# 4channelsRelayv2.net
KiCad netlist of a schematic drawn in EAGLE
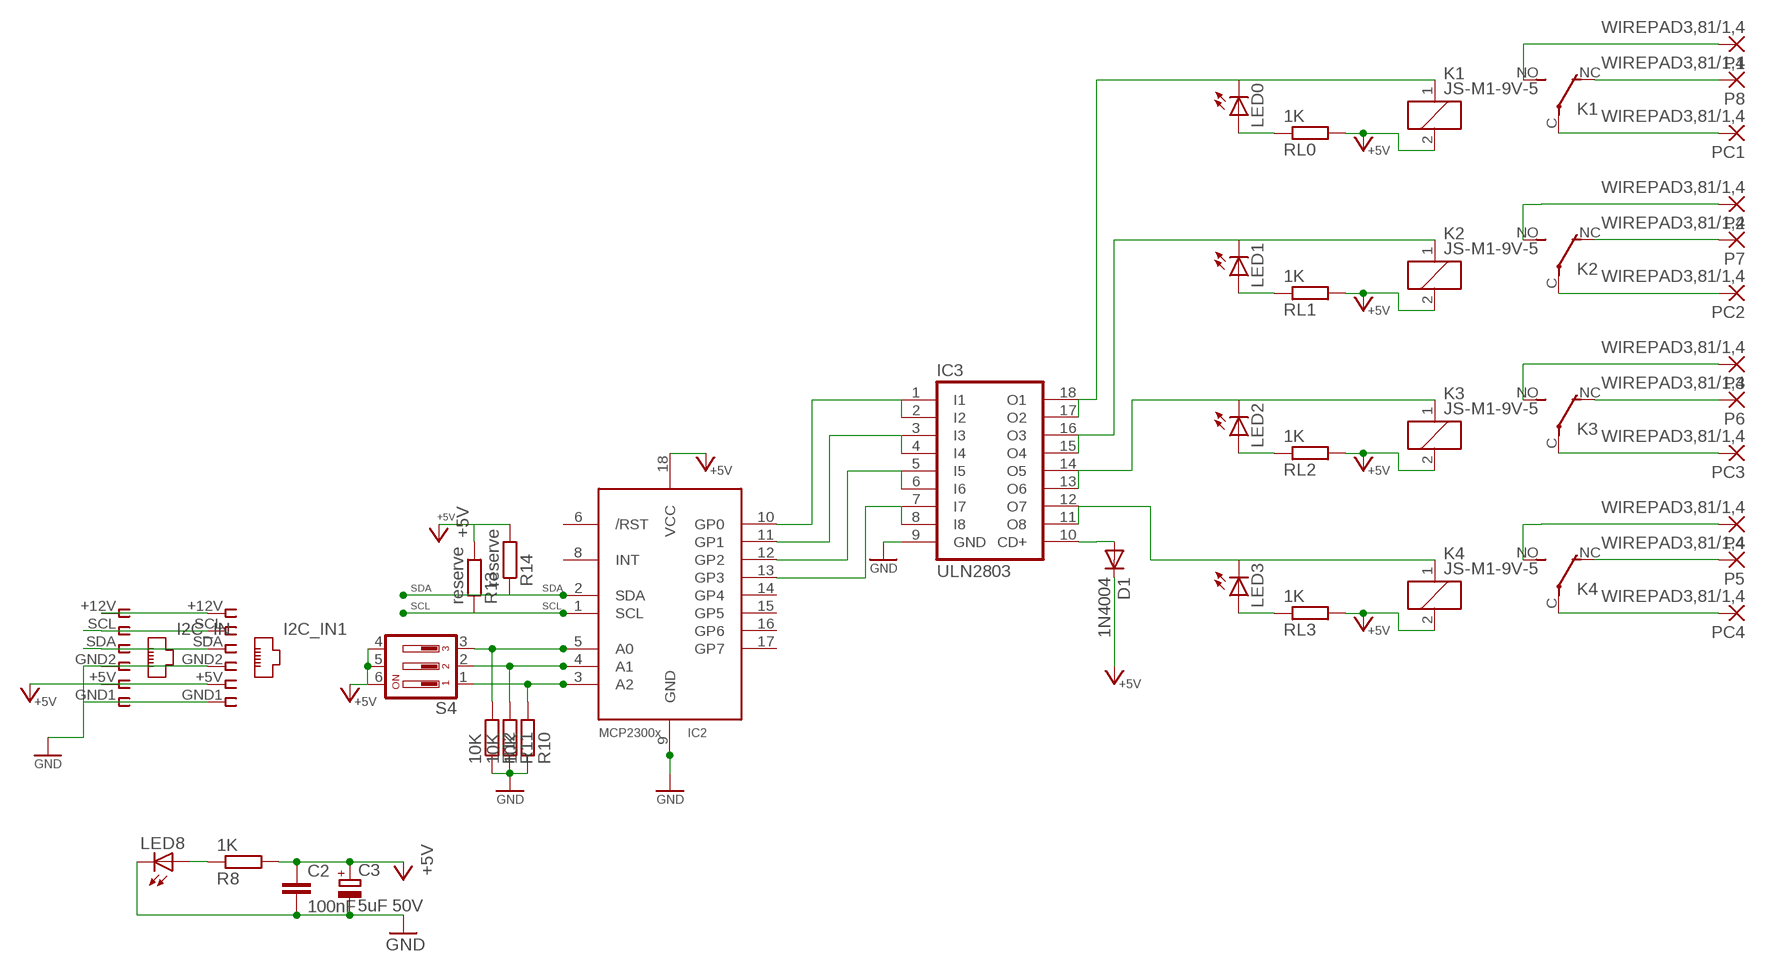
[diagram p0: schematic, sheet 1]

(export (version "E")
  (design (tool "Eeschema 10.0.6"))
  (components
    (comp (ref "C2")
      (value "100nF")
      (footprint "eagle-import:C1206")
      (libsource (lib "eagle-import") (part "C-EUC1206"))
    )
    (comp (ref "C3")
      (value "5uF 50V")
      (footprint "eagle-import:E3,5-8")
      (libsource (lib "eagle-import") (part "CPOL-EUE3.5-8"))
    )
    (comp (ref "D1")
      (value "1N4004")
      (footprint "eagle-import:DO41-10")
      (libsource (lib "eagle-import") (part "1N4004"))
    )
    (comp (ref "I2C_IN")
      (value "I2C 1")
      (footprint "eagle-import:RJ12-STRAIGHT-I2C")
      (libsource (lib "eagle-import") (part "RJ12STRAIGHT-I2C"))
    )
    (comp (ref "I2C_IN1")
      (value "I2C 2")
      (footprint "eagle-import:RJ12-STRAIGHT-I2C")
      (libsource (lib "eagle-import") (part "RJ12STRAIGHT-I2C"))
    )
    (comp (ref "IC2")
      (value "MCP2300X/P")
      (footprint "eagle-import:DIL18")
      (libsource (lib "eagle-import") (part "MCP2300X/P"))
    )
    (comp (ref "IC3")
      (value "ULN2803")
      (footprint "eagle-import:DIL18")
      (libsource (lib "eagle-import") (part "ULN2803A"))
    )
    (comp (ref "K1")
      (value "JS-M1-9V-5")
      (footprint "eagle-import:JS-M")
      (libsource (lib "eagle-import") (part "JS-M1-9V-5"))
    )
    (comp (ref "K2")
      (value "JS-M1-9V-5")
      (footprint "eagle-import:JS-M")
      (libsource (lib "eagle-import") (part "JS-M1-9V-5"))
    )
    (comp (ref "K3")
      (value "JS-M1-9V-5")
      (footprint "eagle-import:JS-M")
      (libsource (lib "eagle-import") (part "JS-M1-9V-5"))
    )
    (comp (ref "K4")
      (value "JS-M1-9V-5")
      (footprint "eagle-import:JS-M")
      (libsource (lib "eagle-import") (part "JS-M1-9V-5"))
    )
    (comp (ref "LED0")
      (value "LED3MM")
      (footprint "eagle-import:LED3MM")
      (libsource (lib "eagle-import") (part "LED3MM"))
    )
    (comp (ref "LED1")
      (value "LED3MM")
      (footprint "eagle-import:LED3MM")
      (libsource (lib "eagle-import") (part "LED3MM"))
    )
    (comp (ref "LED2")
      (value "LED3MM")
      (footprint "eagle-import:LED3MM")
      (libsource (lib "eagle-import") (part "LED3MM"))
    )
    (comp (ref "LED3")
      (value "LED3MM")
      (footprint "eagle-import:LED3MM")
      (libsource (lib "eagle-import") (part "LED3MM"))
    )
    (comp (ref "LED8")
      (value "LED3MM")
      (footprint "eagle-import:LED3MM")
      (libsource (lib "eagle-import") (part "LED3MM"))
    )
    (comp (ref "P1")
      (value "WIREPAD3,81/1,4")
      (footprint "eagle-import:3,81_1,4")
      (libsource (lib "eagle-import") (part "WIREPAD3,81/1,4"))
    )
    (comp (ref "P2")
      (value "WIREPAD3,81/1,4")
      (footprint "eagle-import:3,81_1,4")
      (libsource (lib "eagle-import") (part "WIREPAD3,81/1,4"))
    )
    (comp (ref "P3")
      (value "WIREPAD3,81/1,4")
      (footprint "eagle-import:3,81_1,4")
      (libsource (lib "eagle-import") (part "WIREPAD3,81/1,4"))
    )
    (comp (ref "P4")
      (value "WIREPAD3,81/1,4")
      (footprint "eagle-import:3,81_1,4")
      (libsource (lib "eagle-import") (part "WIREPAD3,81/1,4"))
    )
    (comp (ref "P5")
      (value "WIREPAD3,81/1,4")
      (footprint "eagle-import:3,81_1,4")
      (libsource (lib "eagle-import") (part "WIREPAD3,81/1,4"))
    )
    (comp (ref "P6")
      (value "WIREPAD3,81/1,4")
      (footprint "eagle-import:3,81_1,4")
      (libsource (lib "eagle-import") (part "WIREPAD3,81/1,4"))
    )
    (comp (ref "P7")
      (value "WIREPAD3,81/1,4")
      (footprint "eagle-import:3,81_1,4")
      (libsource (lib "eagle-import") (part "WIREPAD3,81/1,4"))
    )
    (comp (ref "P8")
      (value "WIREPAD3,81/1,4")
      (footprint "eagle-import:3,81_1,4")
      (libsource (lib "eagle-import") (part "WIREPAD3,81/1,4"))
    )
    (comp (ref "PC1")
      (value "WIREPAD3,81/1,4")
      (footprint "eagle-import:3,81_1,4")
      (libsource (lib "eagle-import") (part "WIREPAD3,81/1,4"))
    )
    (comp (ref "PC2")
      (value "WIREPAD3,81/1,4")
      (footprint "eagle-import:3,81_1,4")
      (libsource (lib "eagle-import") (part "WIREPAD3,81/1,4"))
    )
    (comp (ref "PC3")
      (value "WIREPAD3,81/1,4")
      (footprint "eagle-import:3,81_1,4")
      (libsource (lib "eagle-import") (part "WIREPAD3,81/1,4"))
    )
    (comp (ref "PC4")
      (value "WIREPAD3,81/1,4")
      (footprint "eagle-import:3,81_1,4")
      (libsource (lib "eagle-import") (part "WIREPAD3,81/1,4"))
    )
    (comp (ref "R8")
      (value "1K")
      (footprint "eagle-import:M1206")
      (libsource (lib "eagle-import") (part "R-EU_M1206"))
    )
    (comp (ref "R10")
      (value "10K")
      (footprint "eagle-import:M1206")
      (libsource (lib "eagle-import") (part "R-EU_M1206"))
    )
    (comp (ref "R11")
      (value "10K")
      (footprint "eagle-import:M1206")
      (libsource (lib "eagle-import") (part "R-EU_M1206"))
    )
    (comp (ref "R12")
      (value "10K")
      (footprint "eagle-import:M1206")
      (libsource (lib "eagle-import") (part "R-EU_M1206"))
    )
    (comp (ref "R13")
      (value "reserve")
      (footprint "eagle-import:M1206")
      (libsource (lib "eagle-import") (part "R-EU_M1206"))
    )
    (comp (ref "R14")
      (value "reserve")
      (footprint "eagle-import:M1206")
      (libsource (lib "eagle-import") (part "R-EU_M1206"))
    )
    (comp (ref "RL0")
      (value "1K")
      (footprint "eagle-import:M1206")
      (libsource (lib "eagle-import") (part "R-EU_M1206"))
    )
    (comp (ref "RL1")
      (value "1K")
      (footprint "eagle-import:M1206")
      (libsource (lib "eagle-import") (part "R-EU_M1206"))
    )
    (comp (ref "RL2")
      (value "1K")
      (footprint "eagle-import:M1206")
      (libsource (lib "eagle-import") (part "R-EU_M1206"))
    )
    (comp (ref "RL3")
      (value "1K")
      (footprint "eagle-import:M1206")
      (libsource (lib "eagle-import") (part "R-EU_M1206"))
    )
    (comp (ref "S4")
      (value "DIP03YL")
      (footprint "eagle-import:DIP03YL")
      (libsource (lib "eagle-import") (part "DIP03YL"))
    )
  )
  (nets
    (net (code "1") (name "+5V") (class "Default")
      (node (ref "C2") (pin "1") (pinfunction "1_1") (pintype "passive"))
      (node (ref "C3") (pin "+") (pinfunction "+_+") (pintype "passive"))
      (node (ref "D1") (pin "C") (pinfunction "C_C") (pintype "passive"))
      (node (ref "I2C_IN") (pin "+5V") (pinfunction "5_+5V") (pintype "power_in"))
      (node (ref "I2C_IN1") (pin "+5V") (pinfunction "5_+5V") (pintype "power_in"))
      (node (ref "IC2") (pin "18") (pinfunction "VCC_18") (pintype "power_in"))
      (node (ref "K1") (pin "2") (pinfunction "2_2") (pintype "passive"))
      (node (ref "K2") (pin "2") (pinfunction "2_2") (pintype "passive"))
      (node (ref "K3") (pin "2") (pinfunction "2_2") (pintype "passive"))
      (node (ref "K4") (pin "2") (pinfunction "2_2") (pintype "passive"))
      (node (ref "R13") (pin "2") (pinfunction "2_2") (pintype "passive"))
      (node (ref "R14") (pin "2") (pinfunction "2_2") (pintype "passive"))
      (node (ref "R8") (pin "2") (pinfunction "2_2") (pintype "passive"))
      (node (ref "RL0") (pin "2") (pinfunction "2_2") (pintype "passive"))
      (node (ref "RL1") (pin "2") (pinfunction "2_2") (pintype "passive"))
      (node (ref "RL2") (pin "2") (pinfunction "2_2") (pintype "passive"))
      (node (ref "RL3") (pin "2") (pinfunction "2_2") (pintype "passive"))
      (node (ref "S4") (pin "4") (pinfunction "4_4") (pintype "passive"))
      (node (ref "S4") (pin "5") (pinfunction "5_5") (pintype "passive"))
      (node (ref "S4") (pin "6") (pinfunction "6_6") (pintype "passive"))
    )
    (net (code "2") (name "/SCL") (class "Default")
      (node (ref "I2C_IN") (pin "SCL") (pinfunction "2_SCL") (pintype "bidirectional"))
      (node (ref "I2C_IN1") (pin "SCL") (pinfunction "2_SCL") (pintype "bidirectional"))
      (node (ref "IC2") (pin "1") (pinfunction "SCL_1") (pintype "bidirectional"))
      (node (ref "R13") (pin "1") (pinfunction "1_1") (pintype "passive"))
    )
    (net (code "3") (name "/SDA") (class "Default")
      (node (ref "I2C_IN") (pin "SDA") (pinfunction "3_SDA") (pintype "bidirectional"))
      (node (ref "I2C_IN1") (pin "SDA") (pinfunction "3_SDA") (pintype "bidirectional"))
      (node (ref "IC2") (pin "2") (pinfunction "SDA_2") (pintype "bidirectional"))
      (node (ref "R14") (pin "1") (pinfunction "1_1") (pintype "passive"))
    )
    (net (code "4") (name "GND") (class "Default")
      (node (ref "C2") (pin "2") (pinfunction "2_2") (pintype "passive"))
      (node (ref "C3") (pin "-") (pinfunction "-_-") (pintype "passive"))
      (node (ref "I2C_IN") (pin "GND1") (pinfunction "6_GND1") (pintype "power_in"))
      (node (ref "I2C_IN") (pin "GND2") (pinfunction "4_GND2") (pintype "power_in"))
      (node (ref "I2C_IN1") (pin "GND1") (pinfunction "6_GND1") (pintype "power_in"))
      (node (ref "I2C_IN1") (pin "GND2") (pinfunction "4_GND2") (pintype "power_in"))
      (node (ref "IC2") (pin "9") (pinfunction "GND_9") (pintype "power_in"))
      (node (ref "IC3") (pin "9") (pinfunction "GND_9") (pintype "power_in"))
      (node (ref "LED8") (pin "K") (pinfunction "C_K") (pintype "passive"))
      (node (ref "R10") (pin "1") (pinfunction "1_1") (pintype "passive"))
      (node (ref "R11") (pin "1") (pinfunction "1_1") (pintype "passive"))
      (node (ref "R12") (pin "1") (pinfunction "1_1") (pintype "passive"))
    )
    (net (code "5") (name "Net-(I2C_IN-1)") (class "Default")
      (node (ref "I2C_IN") (pin "+12V") (pinfunction "1_+12V") (pintype "power_in"))
      (node (ref "I2C_IN1") (pin "+12V") (pinfunction "1_+12V") (pintype "power_in"))
    )
    (net (code "6") (name "Net-(IC2-A0)") (class "Default")
      (node (ref "IC2") (pin "5") (pinfunction "A0_5") (pintype "input"))
      (node (ref "R12") (pin "2") (pinfunction "2_2") (pintype "passive"))
      (node (ref "S4") (pin "3") (pinfunction "3_3") (pintype "passive"))
    )
    (net (code "7") (name "Net-(IC2-A1)") (class "Default")
      (node (ref "IC2") (pin "4") (pinfunction "A1_4") (pintype "input"))
      (node (ref "R11") (pin "2") (pinfunction "2_2") (pintype "passive"))
      (node (ref "S4") (pin "2") (pinfunction "2_2") (pintype "passive"))
    )
    (net (code "8") (name "Net-(IC2-A2)") (class "Default")
      (node (ref "IC2") (pin "3") (pinfunction "A2_3") (pintype "input"))
      (node (ref "R10") (pin "2") (pinfunction "2_2") (pintype "passive"))
      (node (ref "S4") (pin "1") (pinfunction "1_1") (pintype "passive"))
    )
    (net (code "9") (name "Net-(IC2-GP0)") (class "Default")
      (node (ref "IC2") (pin "10") (pinfunction "GP0_10") (pintype "bidirectional"))
      (node (ref "IC3") (pin "1") (pinfunction "I1_1") (pintype "input"))
      (node (ref "IC3") (pin "2") (pinfunction "I2_2") (pintype "input"))
    )
    (net (code "10") (name "Net-(IC2-GP1)") (class "Default")
      (node (ref "IC2") (pin "11") (pinfunction "GP1_11") (pintype "bidirectional"))
      (node (ref "IC3") (pin "3") (pinfunction "I3_3") (pintype "input"))
      (node (ref "IC3") (pin "4") (pinfunction "I4_4") (pintype "input"))
    )
    (net (code "11") (name "Net-(IC2-GP2)") (class "Default")
      (node (ref "IC2") (pin "12") (pinfunction "GP2_12") (pintype "bidirectional"))
      (node (ref "IC3") (pin "5") (pinfunction "I5_5") (pintype "input"))
      (node (ref "IC3") (pin "6") (pinfunction "I6_6") (pintype "input"))
    )
    (net (code "12") (name "Net-(IC2-GP3)") (class "Default")
      (node (ref "IC2") (pin "13") (pinfunction "GP3_13") (pintype "bidirectional"))
      (node (ref "IC3") (pin "7") (pinfunction "I7_7") (pintype "input"))
      (node (ref "IC3") (pin "8") (pinfunction "I8_8") (pintype "input"))
    )
    (net (code "13") (name "Net-(IC3-CD+)") (class "Default")
      (node (ref "D1") (pin "A") (pinfunction "A_A") (pintype "passive"))
      (node (ref "IC3") (pin "10") (pinfunction "CD+_10") (pintype "passive"))
    )
    (net (code "14") (name "Net-(IC3-O1)") (class "Default")
      (node (ref "IC3") (pin "17") (pinfunction "O2_17") (pintype "open_collector"))
      (node (ref "IC3") (pin "18") (pinfunction "O1_18") (pintype "open_collector"))
      (node (ref "K1") (pin "1") (pinfunction "1_1") (pintype "passive"))
      (node (ref "LED0") (pin "K") (pinfunction "C_K") (pintype "passive"))
    )
    (net (code "15") (name "Net-(IC3-O3)") (class "Default")
      (node (ref "IC3") (pin "15") (pinfunction "O4_15") (pintype "open_collector"))
      (node (ref "IC3") (pin "16") (pinfunction "O3_16") (pintype "open_collector"))
      (node (ref "K2") (pin "1") (pinfunction "1_1") (pintype "passive"))
      (node (ref "LED1") (pin "K") (pinfunction "C_K") (pintype "passive"))
    )
    (net (code "16") (name "Net-(IC3-O5)") (class "Default")
      (node (ref "IC3") (pin "13") (pinfunction "O6_13") (pintype "open_collector"))
      (node (ref "IC3") (pin "14") (pinfunction "O5_14") (pintype "open_collector"))
      (node (ref "K3") (pin "1") (pinfunction "1_1") (pintype "passive"))
      (node (ref "LED2") (pin "K") (pinfunction "C_K") (pintype "passive"))
    )
    (net (code "17") (name "Net-(IC3-O7)") (class "Default")
      (node (ref "IC3") (pin "11") (pinfunction "O8_11") (pintype "open_collector"))
      (node (ref "IC3") (pin "12") (pinfunction "O7_12") (pintype "open_collector"))
      (node (ref "K4") (pin "1") (pinfunction "1_1") (pintype "passive"))
      (node (ref "LED3") (pin "K") (pinfunction "C_K") (pintype "passive"))
    )
    (net (code "18") (name "Net-(K1B-O)") (class "Default")
      (node (ref "K1") (pin "NC") (pinfunction "O_NC") (pintype "passive"))
      (node (ref "P8") (pin "1") (pinfunction "P_1") (pintype "passive"))
    )
    (net (code "19") (name "Net-(K1B-P)") (class "Default")
      (node (ref "K1") (pin "C") (pinfunction "P_C") (pintype "passive"))
      (node (ref "PC1") (pin "1") (pinfunction "P_1") (pintype "passive"))
    )
    (net (code "20") (name "Net-(K1B-S)") (class "Default")
      (node (ref "K1") (pin "NO") (pinfunction "S_NO") (pintype "passive"))
      (node (ref "P1") (pin "1") (pinfunction "P_1") (pintype "passive"))
    )
    (net (code "21") (name "Net-(K2B-O)") (class "Default")
      (node (ref "K2") (pin "NC") (pinfunction "O_NC") (pintype "passive"))
      (node (ref "P7") (pin "1") (pinfunction "P_1") (pintype "passive"))
    )
    (net (code "22") (name "Net-(K2B-P)") (class "Default")
      (node (ref "K2") (pin "C") (pinfunction "P_C") (pintype "passive"))
      (node (ref "PC2") (pin "1") (pinfunction "P_1") (pintype "passive"))
    )
    (net (code "23") (name "Net-(K2B-S)") (class "Default")
      (node (ref "K2") (pin "NO") (pinfunction "S_NO") (pintype "passive"))
      (node (ref "P2") (pin "1") (pinfunction "P_1") (pintype "passive"))
    )
    (net (code "24") (name "Net-(K3B-O)") (class "Default")
      (node (ref "K3") (pin "NC") (pinfunction "O_NC") (pintype "passive"))
      (node (ref "P6") (pin "1") (pinfunction "P_1") (pintype "passive"))
    )
    (net (code "25") (name "Net-(K3B-P)") (class "Default")
      (node (ref "K3") (pin "C") (pinfunction "P_C") (pintype "passive"))
      (node (ref "PC3") (pin "1") (pinfunction "P_1") (pintype "passive"))
    )
    (net (code "26") (name "Net-(K3B-S)") (class "Default")
      (node (ref "K3") (pin "NO") (pinfunction "S_NO") (pintype "passive"))
      (node (ref "P3") (pin "1") (pinfunction "P_1") (pintype "passive"))
    )
    (net (code "27") (name "Net-(K4B-O)") (class "Default")
      (node (ref "K4") (pin "NC") (pinfunction "O_NC") (pintype "passive"))
      (node (ref "P5") (pin "1") (pinfunction "P_1") (pintype "passive"))
    )
    (net (code "28") (name "Net-(K4B-P)") (class "Default")
      (node (ref "K4") (pin "C") (pinfunction "P_C") (pintype "passive"))
      (node (ref "PC4") (pin "1") (pinfunction "P_1") (pintype "passive"))
    )
    (net (code "29") (name "Net-(K4B-S)") (class "Default")
      (node (ref "K4") (pin "NO") (pinfunction "S_NO") (pintype "passive"))
      (node (ref "P4") (pin "1") (pinfunction "P_1") (pintype "passive"))
    )
    (net (code "30") (name "Net-(LED0-PadA)") (class "Default")
      (node (ref "LED0") (pin "A") (pinfunction "A_A") (pintype "passive"))
      (node (ref "RL0") (pin "1") (pinfunction "1_1") (pintype "passive"))
    )
    (net (code "31") (name "Net-(LED1-PadA)") (class "Default")
      (node (ref "LED1") (pin "A") (pinfunction "A_A") (pintype "passive"))
      (node (ref "RL1") (pin "1") (pinfunction "1_1") (pintype "passive"))
    )
    (net (code "32") (name "Net-(LED2-PadA)") (class "Default")
      (node (ref "LED2") (pin "A") (pinfunction "A_A") (pintype "passive"))
      (node (ref "RL2") (pin "1") (pinfunction "1_1") (pintype "passive"))
    )
    (net (code "33") (name "Net-(LED3-PadA)") (class "Default")
      (node (ref "LED3") (pin "A") (pinfunction "A_A") (pintype "passive"))
      (node (ref "RL3") (pin "1") (pinfunction "1_1") (pintype "passive"))
    )
    (net (code "34") (name "Net-(LED8-PadA)") (class "Default")
      (node (ref "LED8") (pin "A") (pinfunction "A_A") (pintype "passive"))
      (node (ref "R8") (pin "1") (pinfunction "1_1") (pintype "passive"))
    )
    (net (code "35") (name "unconnected-(IC2-GP4-Pad14)") (class "Default")
      (node (ref "IC2") (pin "14") (pinfunction "GP4_14") (pintype "bidirectional"))
    )
    (net (code "36") (name "unconnected-(IC2-GP5-Pad15)") (class "Default")
      (node (ref "IC2") (pin "15") (pinfunction "GP5_15") (pintype "bidirectional"))
    )
    (net (code "37") (name "unconnected-(IC2-GP6-Pad16)") (class "Default")
      (node (ref "IC2") (pin "16") (pinfunction "GP6_16") (pintype "bidirectional"))
    )
    (net (code "38") (name "unconnected-(IC2-GP7-Pad17)") (class "Default")
      (node (ref "IC2") (pin "17") (pinfunction "GP7_17") (pintype "bidirectional"))
    )
    (net (code "39") (name "unconnected-(IC2-INT-Pad8)") (class "Default")
      (node (ref "IC2") (pin "8") (pinfunction "INT_8") (pintype "output"))
    )
    (net (code "40") (name "unconnected-(IC2-{slash}RST-Pad6)") (class "Default")
      (node (ref "IC2") (pin "6") (pinfunction "/RST_6") (pintype "input"))
    )
  )
)
